# Microcontroller.net
KiCad netlist of a schematic drawn in Altium Designer
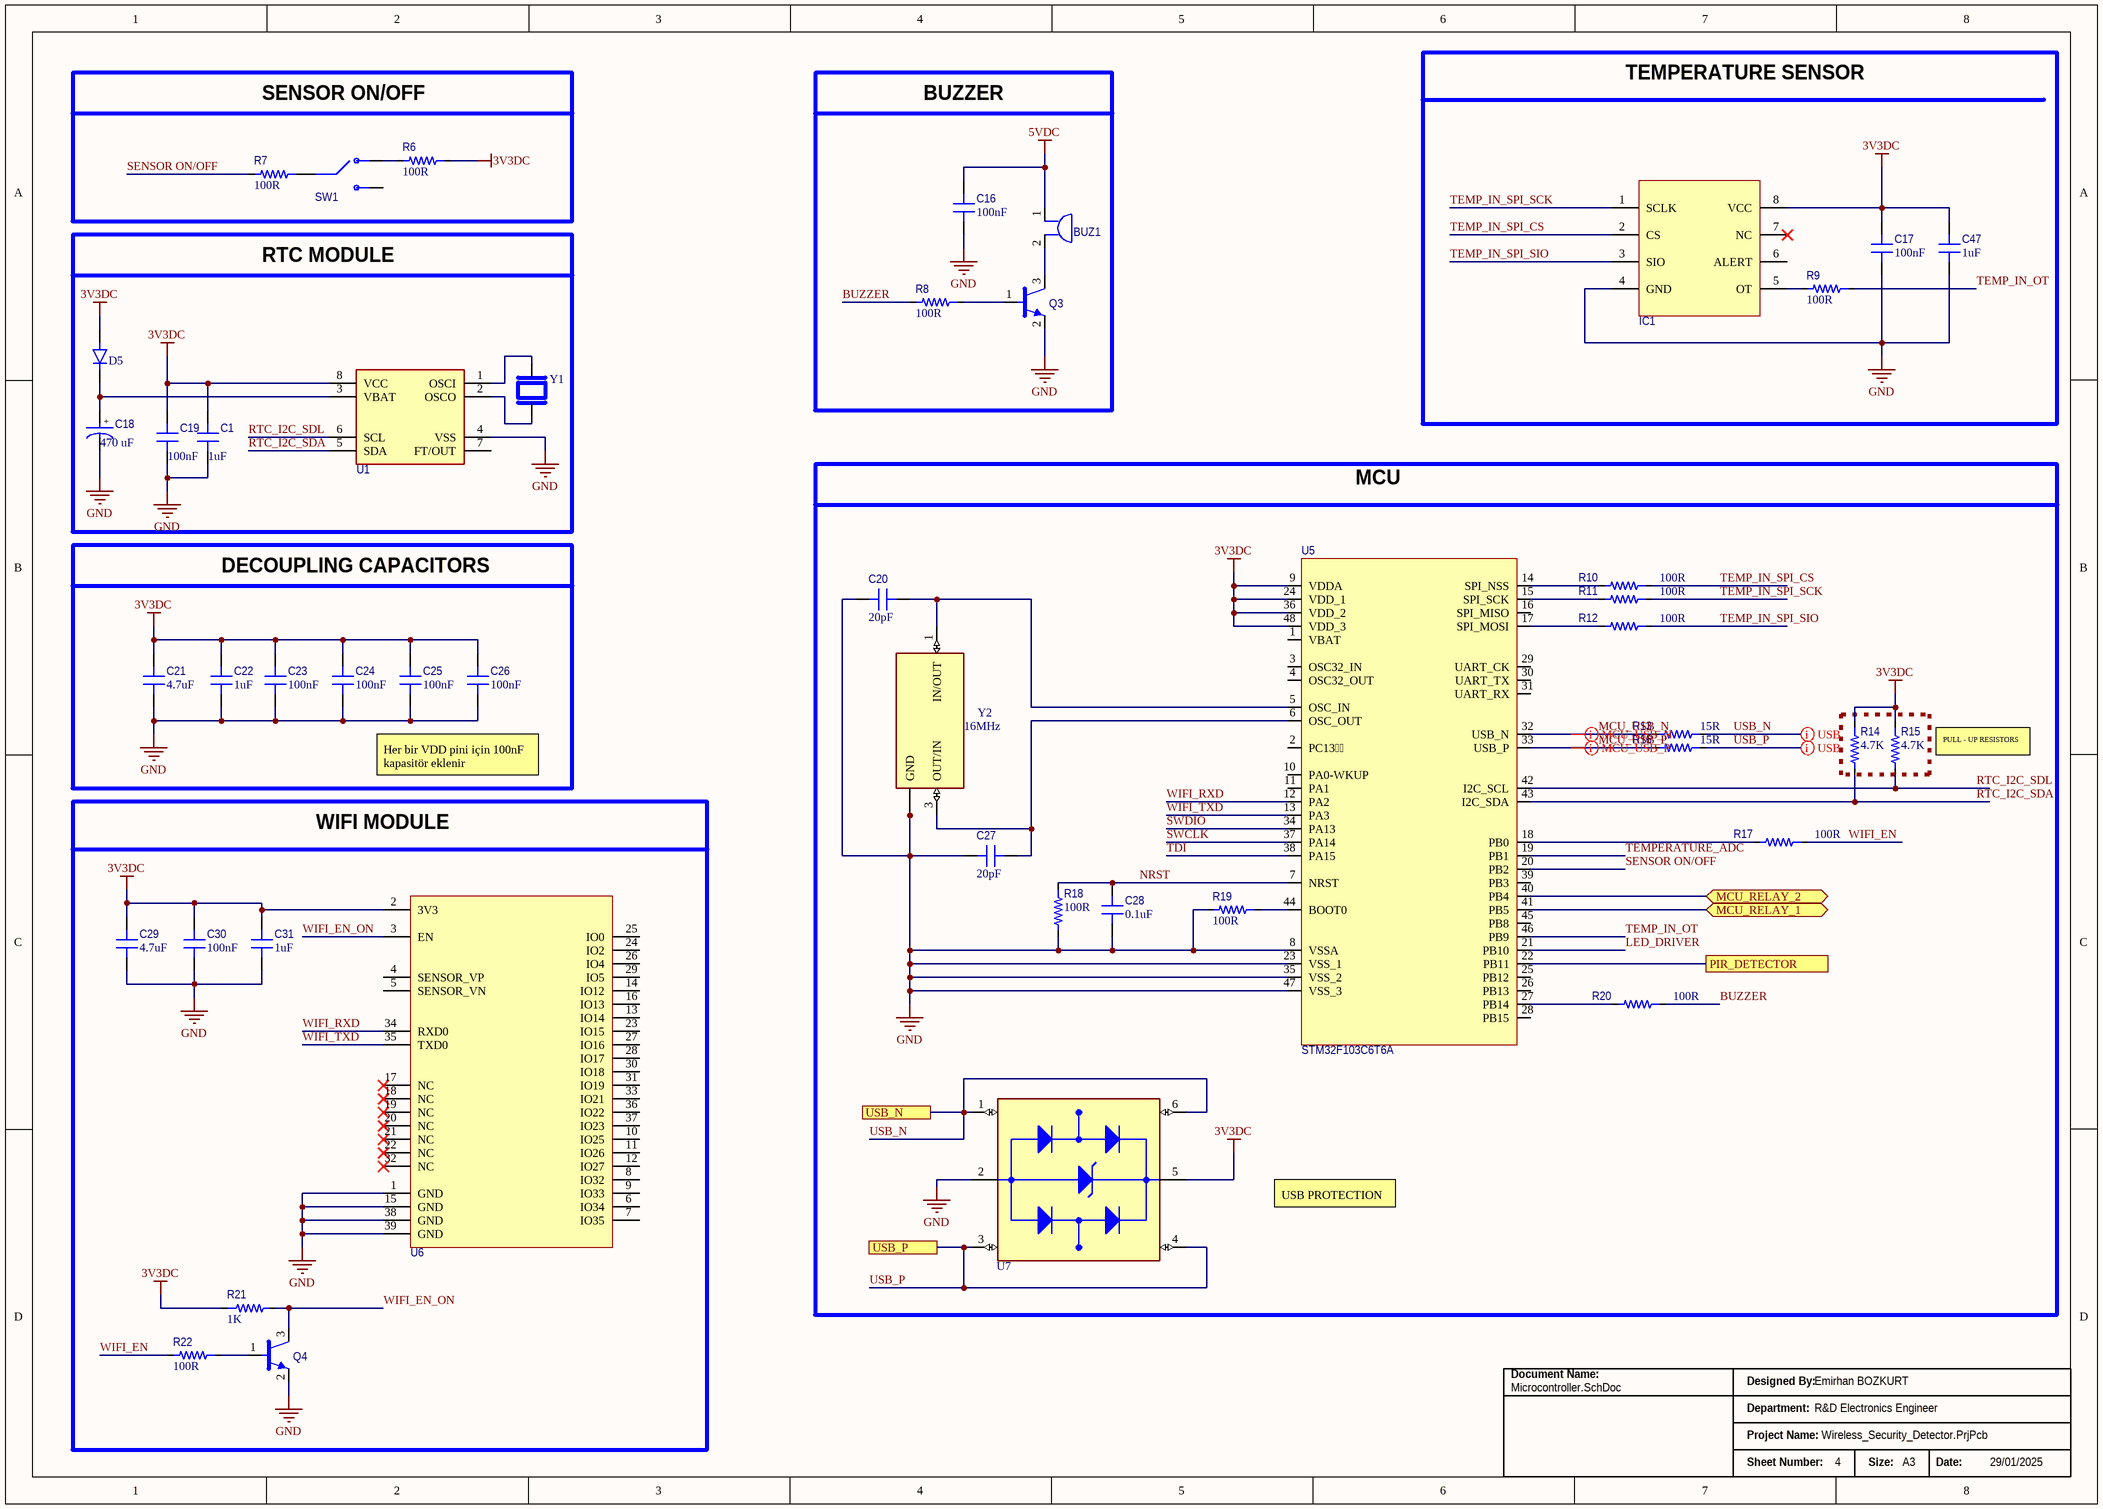
[diagram p0: Microcontroller.SchDoc]

(export (version "E")
  (design (tool "Eeschema 10.0.6"))
  (components
    (comp (ref "BUZ1")
      (value "CMI-9605IC-0580T")
      (footprint "CMI-9605IC-0580T")
      (description "BUZZER MAGNETIC 5V 9.6MM TH")
      (fields (field (name "DESIGNED BY") "Emirhan Bozkurt"))
      (libsource (lib "Emirhan's") (part "CMI-9605IC-0580T"))
    )
    (comp (ref "C1")
      (value "1uF")
      (footprint "CAP_0805")
      (description "CAP CER 1uF 25V X5R 0805")
      (fields
        (field (name "MANUFACTURER") "Samsung Electro-Mechanics")
        (field (name "Comment") "CL21B105KBFNNNE")
        (field (name "DESIGNED BY") "Emirhan Bozkurt")
      )
      (libsource (lib "Emirhan's") (part "CAP CER 1uF 0805"))
    )
    (comp (ref "C16")
      (value "100nF")
      (footprint "CAP_0805")
      (description "CAP CER 0.1uF 50V X7R 0805")
      (fields (field (name "Comment") "1276-1003-2-ND") (field (name "DESIGNED BY") "Emirhan Bozkurt"))
      (libsource (lib "Emirhan's") (part "CAP CER 100nF 0805"))
    )
    (comp (ref "C17")
      (value "100nF")
      (footprint "CAP_0805")
      (description "CAP CER 0.1uF 50V X7R 0805")
      (fields (field (name "Comment") "1276-1003-2-ND") (field (name "DESIGNED BY") "Emirhan Bozkurt"))
      (libsource (lib "Emirhan's") (part "CAP CER 100nF 0805"))
    )
    (comp (ref "C18")
      (value "470 uF")
      (footprint "CAP_ALU_470UF_SMD")
      (description "CAP ALUM POLY 470uF 20% 25V SMD")
      (fields
        (field (name "MANUFACTURER") "Nichicon")
        (field (name "Comment") "PCR1E471MCL1GS")
        (field (name "DESIGNED BY") "Emirhan Bozkurt")
      )
      (libsource (lib "Emirhan's") (part "CAP ALU 470uF SMD"))
    )
    (comp (ref "C19")
      (value "100nF")
      (footprint "CAP_0805")
      (description "CAP CER 0.1uF 50V X7R 0805")
      (fields (field (name "Comment") "1276-1003-2-ND") (field (name "DESIGNED BY") "Emirhan Bozkurt"))
      (libsource (lib "Emirhan's") (part "CAP CER 100nF 0805"))
    )
    (comp (ref "C20")
      (value "20pF")
      (footprint "CAP_0603")
      (description "CAP CER 20pF 50V C0G/NP0 0603")
      (fields
        (field (name "MANUFACTURER") "Samsung Electro-Mechanics")
        (field (name "Comment") "C0603C104K4RACTU")
        (field (name "DESIGNED BY") "Emirhan Bozkurt")
      )
      (libsource (lib "Emirhan's") (part "CAP CER 20pF 0603"))
    )
    (comp (ref "C21")
      (value "4.7uF")
      (footprint "CAP_0805")
      (description "CAP CER 4.7uF 25V X5R 0805")
      (fields
        (field (name "MANUFACTURER") "Samsung Electro-Mechanics")
        (field (name "Comment") "CL21A475KAQNNNE")
        (field (name "DESIGNED BY") "Emirhan Bozkurt")
      )
      (libsource (lib "Emirhan's") (part "CAP CER 4.7uF 0805"))
    )
    (comp (ref "C22")
      (value "1uF")
      (footprint "CAP_0805")
      (description "CAP CER 1uF 25V X5R 0805")
      (fields
        (field (name "MANUFACTURER") "Samsung Electro-Mechanics")
        (field (name "Comment") "CL21B105KBFNNNE")
        (field (name "DESIGNED BY") "Emirhan Bozkurt")
      )
      (libsource (lib "Emirhan's") (part "CAP CER 1uF 0805"))
    )
    (comp (ref "C23")
      (value "100nF")
      (footprint "CAP_0805")
      (description "CAP CER 0.1uF 50V X7R 0805")
      (fields (field (name "Comment") "1276-1003-2-ND") (field (name "DESIGNED BY") "Emirhan Bozkurt"))
      (libsource (lib "Emirhan's") (part "CAP CER 100nF 0805"))
    )
    (comp (ref "C24")
      (value "100nF")
      (footprint "CAP_0805")
      (description "CAP CER 0.1uF 50V X7R 0805")
      (fields (field (name "Comment") "1276-1003-2-ND") (field (name "DESIGNED BY") "Emirhan Bozkurt"))
      (libsource (lib "Emirhan's") (part "CAP CER 100nF 0805"))
    )
    (comp (ref "C25")
      (value "100nF")
      (footprint "CAP_0805")
      (description "CAP CER 0.1uF 50V X7R 0805")
      (fields (field (name "Comment") "1276-1003-2-ND") (field (name "DESIGNED BY") "Emirhan Bozkurt"))
      (libsource (lib "Emirhan's") (part "CAP CER 100nF 0805"))
    )
    (comp (ref "C26")
      (value "100nF")
      (footprint "CAP_0805")
      (description "CAP CER 0.1uF 50V X7R 0805")
      (fields (field (name "Comment") "1276-1003-2-ND") (field (name "DESIGNED BY") "Emirhan Bozkurt"))
      (libsource (lib "Emirhan's") (part "CAP CER 100nF 0805"))
    )
    (comp (ref "C27")
      (value "20pF")
      (footprint "CAP_0603")
      (description "CAP CER 20pF 50V C0G/NP0 0603")
      (fields
        (field (name "MANUFACTURER") "Samsung Electro-Mechanics")
        (field (name "Comment") "C0603C104K4RACTU")
        (field (name "DESIGNED BY") "Emirhan Bozkurt")
      )
      (libsource (lib "Emirhan's") (part "CAP CER 20pF 0603"))
    )
    (comp (ref "C28")
      (value "0.1uF")
      (footprint "CAP_0603")
      (description "CAP CER 0.1uF 16V X7R 0603")
      (fields
        (field (name "MANUFACTURER") "Samsung Electro-Mechanics")
        (field (name "Comment") "C0603C104K4RACTU")
        (field (name "DESIGNED BY") "Emirhan Bozkurt")
      )
      (libsource (lib "Emirhan's") (part "CAP CER 0.1uF 0603"))
    )
    (comp (ref "C29")
      (value "4.7uF")
      (footprint "CAP_0805")
      (description "CAP CER 4.7uF 25V X5R 0805")
      (fields
        (field (name "MANUFACTURER") "Samsung Electro-Mechanics")
        (field (name "Comment") "CL21A475KAQNNNE")
        (field (name "DESIGNED BY") "Emirhan Bozkurt")
      )
      (libsource (lib "Emirhan's") (part "CAP CER 4.7uF 0805"))
    )
    (comp (ref "C30")
      (value "100nF")
      (footprint "CAP_0805")
      (description "CAP CER 0.1uF 50V X7R 0805")
      (fields (field (name "Comment") "1276-1003-2-ND") (field (name "DESIGNED BY") "Emirhan Bozkurt"))
      (libsource (lib "Emirhan's") (part "CAP CER 100nF 0805"))
    )
    (comp (ref "C31")
      (value "1uF")
      (footprint "CAP_0805")
      (description "CAP CER 1uF 25V X5R 0805")
      (fields
        (field (name "MANUFACTURER") "Samsung Electro-Mechanics")
        (field (name "Comment") "CL21B105KBFNNNE")
        (field (name "DESIGNED BY") "Emirhan Bozkurt")
      )
      (libsource (lib "Emirhan's") (part "CAP CER 1uF 0805"))
    )
    (comp (ref "C47")
      (value "1uF")
      (footprint "CAP_0805")
      (description "CAP CER 1uF 25V X5R 0805")
      (fields
        (field (name "MANUFACTURER") "Samsung Electro-Mechanics")
        (field (name "Comment") "CL21B105KBFNNNE")
        (field (name "DESIGNED BY") "Emirhan Bozkurt")
      )
      (libsource (lib "Emirhan's") (part "CAP CER 1uF 0805"))
    )
    (comp (ref "D5")
      (value "1N4148WS")
      (footprint "1N4148WS")
      (description "DIODE STANDARD 75V 150MA SOD323F")
      (fields
        (field (name "MANUFACTURER") "Diotec Semiconductor")
        (field (name "DESIGNED BY") "Emirhan Bozkurt")
      )
      (libsource (lib "Emirhan's") (part "1N4148WS"))
    )
    (comp (ref "IC1")
      (value "MAX6662MSA+")
      (footprint "SOIC-8")
      (description "TEMPERATURE SENSOR DIGITAL REMOTE 8SOIC")
      (fields (field (name "DESIGNED BY") "Emirhan Bozkurt"))
      (libsource (lib "Emirhan's") (part "MAX6662MSA+"))
    )
    (comp (ref "Q3")
      (value "MMBT3904-7-F")
      (footprint "SOT-23F")
      (description "TRANS NPN 40V 0.2A SOT-23-3")
      (libsource (lib "Emirhan's") (part "MMBT3904-7-F"))
    )
    (comp (ref "Q4")
      (value "MMBT3904-7-F")
      (footprint "SOT-23F")
      (description "TRANS NPN 40V 0.2A SOT-23-3")
      (libsource (lib "Emirhan's") (part "MMBT3904-7-F"))
    )
    (comp (ref "R6")
      (value "100R")
      (footprint "RES_0603")
      (description "RES 100 OHM 1% 1/10W 0603")
      (fields
        (field (name "SUPPIER PART NUMBER") "311-100HRTR-ND")
        (field (name "MANUFACTURER") "YAGEO")
        (field (name "DESIGNED BY") "Emirhan Bozkurt")
      )
      (libsource (lib "Emirhan's") (part "RES 100R 0603"))
    )
    (comp (ref "R7")
      (value "100R")
      (footprint "RES_0603")
      (description "RES 100 OHM 1% 1/10W 0603")
      (fields
        (field (name "SUPPIER PART NUMBER") "311-100HRTR-ND")
        (field (name "MANUFACTURER") "YAGEO")
        (field (name "DESIGNED BY") "Emirhan Bozkurt")
      )
      (libsource (lib "Emirhan's") (part "RES 100R 0603"))
    )
    (comp (ref "R8")
      (value "100R")
      (footprint "RES_0603")
      (description "RES 100 OHM 1% 1/10W 0603")
      (fields
        (field (name "SUPPIER PART NUMBER") "311-100HRTR-ND")
        (field (name "MANUFACTURER") "YAGEO")
        (field (name "DESIGNED BY") "Emirhan Bozkurt")
      )
      (libsource (lib "Emirhan's") (part "RES 100R 0603"))
    )
    (comp (ref "R9")
      (value "100R")
      (footprint "RES_0603")
      (description "RES 100 OHM 1% 1/10W 0603")
      (fields
        (field (name "SUPPIER PART NUMBER") "311-100HRTR-ND")
        (field (name "MANUFACTURER") "YAGEO")
        (field (name "DESIGNED BY") "Emirhan Bozkurt")
      )
      (libsource (lib "Emirhan's") (part "RES 100R 0603"))
    )
    (comp (ref "R10")
      (value "100R")
      (footprint "RES_0603")
      (description "RES 100 OHM 1% 1/10W 0603")
      (fields
        (field (name "SUPPIER PART NUMBER") "311-100HRTR-ND")
        (field (name "MANUFACTURER") "YAGEO")
        (field (name "DESIGNED BY") "Emirhan Bozkurt")
      )
      (libsource (lib "Emirhan's") (part "RES 100R 0603"))
    )
    (comp (ref "R11")
      (value "100R")
      (footprint "RES_0603")
      (description "RES 100 OHM 1% 1/10W 0603")
      (fields
        (field (name "SUPPIER PART NUMBER") "311-100HRTR-ND")
        (field (name "MANUFACTURER") "YAGEO")
        (field (name "DESIGNED BY") "Emirhan Bozkurt")
      )
      (libsource (lib "Emirhan's") (part "RES 100R 0603"))
    )
    (comp (ref "R12")
      (value "100R")
      (footprint "RES_0603")
      (description "RES 100 OHM 1% 1/10W 0603")
      (fields
        (field (name "SUPPIER PART NUMBER") "311-100HRTR-ND")
        (field (name "MANUFACTURER") "YAGEO")
        (field (name "DESIGNED BY") "Emirhan Bozkurt")
      )
      (libsource (lib "Emirhan's") (part "RES 100R 0603"))
    )
    (comp (ref "R13")
      (value "15R")
      (footprint "RES_0603")
      (description "RES 15 OHM 1% 1/10W 0603")
      (fields
        (field (name "SUPPIER PART NUMBER") "311-15.0HRTR-ND")
        (field (name "MANUFACTURER") "YAGEO")
        (field (name "DESIGNED BY") "Emirhan Bozkurt")
      )
      (libsource (lib "Emirhan's") (part "RES 15R 0603"))
    )
    (comp (ref "R14")
      (value "4.7K")
      (footprint "RES_0603")
      (description "RES 4K7 OHM 1% 1/10W 0603")
      (fields
        (field (name "SUPPIER PART NUMBER") "311-4.70KHRCT-ND")
        (field (name "MANUFACTURER") "YAGEO")
        (field (name "DESIGNED BY") "Emirhan Bozkurt")
      )
      (libsource (lib "Emirhan's") (part "RES 4K7 0603"))
    )
    (comp (ref "R15")
      (value "4.7K")
      (footprint "RES_0603")
      (description "RES 4K7 OHM 1% 1/10W 0603")
      (fields
        (field (name "SUPPIER PART NUMBER") "311-4.70KHRCT-ND")
        (field (name "MANUFACTURER") "YAGEO")
        (field (name "DESIGNED BY") "Emirhan Bozkurt")
      )
      (libsource (lib "Emirhan's") (part "RES 4K7 0603"))
    )
    (comp (ref "R16")
      (value "15R")
      (footprint "RES_0603")
      (description "RES 15 OHM 1% 1/10W 0603")
      (fields
        (field (name "SUPPIER PART NUMBER") "311-15.0HRTR-ND")
        (field (name "MANUFACTURER") "YAGEO")
        (field (name "DESIGNED BY") "Emirhan Bozkurt")
      )
      (libsource (lib "Emirhan's") (part "RES 15R 0603"))
    )
    (comp (ref "R17")
      (value "100R")
      (footprint "RES_0603")
      (description "RES 100 OHM 1% 1/10W 0603")
      (fields
        (field (name "SUPPIER PART NUMBER") "311-100HRTR-ND")
        (field (name "MANUFACTURER") "YAGEO")
        (field (name "DESIGNED BY") "Emirhan Bozkurt")
      )
      (libsource (lib "Emirhan's") (part "RES 100R 0603"))
    )
    (comp (ref "R18")
      (value "100R")
      (footprint "RES_0603")
      (description "RES 100 OHM 1% 1/10W 0603")
      (fields
        (field (name "SUPPIER PART NUMBER") "311-100HRTR-ND")
        (field (name "MANUFACTURER") "YAGEO")
        (field (name "DESIGNED BY") "Emirhan Bozkurt")
      )
      (libsource (lib "Emirhan's") (part "RES 100R 0603"))
    )
    (comp (ref "R19")
      (value "100R")
      (footprint "RES_0603")
      (description "RES 100 OHM 1% 1/10W 0603")
      (fields
        (field (name "SUPPIER PART NUMBER") "311-100HRTR-ND")
        (field (name "MANUFACTURER") "YAGEO")
        (field (name "DESIGNED BY") "Emirhan Bozkurt")
      )
      (libsource (lib "Emirhan's") (part "RES 100R 0603"))
    )
    (comp (ref "R20")
      (value "100R")
      (footprint "RES_0603")
      (description "RES 100 OHM 1% 1/10W 0603")
      (fields
        (field (name "SUPPIER PART NUMBER") "311-100HRTR-ND")
        (field (name "MANUFACTURER") "YAGEO")
        (field (name "DESIGNED BY") "Emirhan Bozkurt")
      )
      (libsource (lib "Emirhan's") (part "RES 100R 0603"))
    )
    (comp (ref "R21")
      (value "1K")
      (footprint "RES_0603")
      (description "RES 1K 1% 1/10W 0603")
      (fields
        (field (name "SUPPIER PART NUMBER") "311-1.00KHRCT-ND")
        (field (name "MANUFACTURER") "YAGEO")
        (field (name "DESIGNED BY") "Emirhan Bozkurt")
      )
      (libsource (lib "Emirhan's") (part "RES 1K 0603"))
    )
    (comp (ref "R22")
      (value "100R")
      (footprint "RES_0603")
      (description "RES 100 OHM 1% 1/10W 0603")
      (fields
        (field (name "SUPPIER PART NUMBER") "311-100HRTR-ND")
        (field (name "MANUFACTURER") "YAGEO")
        (field (name "DESIGNED BY") "Emirhan Bozkurt")
      )
      (libsource (lib "Emirhan's") (part "RES 100R 0603"))
    )
    (comp (ref "SW1")
      (value "EG1215AA")
      (footprint "EG1215AA")
      (description "SWITCH SLIDE SPDT 25MA 24V")
      (fields (field (name "DESIGNED BY") "Emirhan Bozkurt"))
      (libsource (lib "Emirhan's") (part "EG1215AA"))
    )
    (comp (ref "U1")
      (value "M41T00M6F")
      (footprint "SOIC-8")
      (description "IC RTC CLK/CALENDAR I2C 8SOIC")
      (fields (field (name "DESIGNED BY") "Emirhan BOZKURT"))
      (libsource (lib "Emirhan's") (part "M41T00M6F"))
    )
    (comp (ref "U5")
      (value "STM32F103C6T6A")
      (footprint "LQFP-48")
      (description "IC MCU 32BIT 32KB FLASH 48LQFP")
      (fields (field (name "VOLTAGE") "2V ~ 3.6V") (field (name "DESIGNED BY") "Emirhan Bozkurt"))
      (libsource (lib "Emirhan's") (part "STM32F103C6T6A"))
    )
    (comp (ref "U6")
      (value "ESP32-WROOM-32E-N4")
      (footprint "ESP32-WROOM-32E")
      (description "RF TXRX MOD BT WIFI TH SMD")
      (fields (field (name "DESIGNED BY") "Emirhan Bozkurt"))
      (libsource (lib "Emirhan's") (part "ESP32-WROOM-32E-N4"))
    )
    (comp (ref "U7")
      (value "USBLC6-2SC6")
      (footprint "SOT95P280X145-6N")
      (description "TVS DIODE 5.25VWM 17VC SOT23-6")
      (fields
        (field (name "MANUFACTURER") "STMicroelectronics")
        (field (name "DESIGNED BY") "Emirhan Bozkurt")
      )
      (libsource (lib "Emirhan's") (part "USB PROTECTION"))
    )
    (comp (ref "Y1")
      (value "ABS05-32.768KHZ-T")
      (footprint "XTAL_ABS05-32.768KHZ-T")
      (description "CRYSTAL 32.7680KHZ 12.5PF SMD")
      (fields
        (field (name "SUPPLER PART NUMBER") "535-11899-2-ND")
        (field (name "DESIGNED BY") "Emirhan Bozkurt")
      )
      (libsource (lib "Emirhan's") (part "ABS05-32.768KHZ-T"))
    )
    (comp (ref "Y2")
      (value "16MHz")
      (footprint "XTAL_ECS-160-20-30B-TR")
      (description "CRYSTAL 16.0000MHZ 20PF SMD")
      (fields (field (name "Comment") "ECS-160-20-30B-TR") (field (name "DESIGNED BY") "Emirhan Bozkurt"))
      (libsource (lib "Emirhan's") (part "ECS-160-20-30B-TR"))
    )
  )
  (nets
    (net (code "1") (name "/BUZZER") (class "Default")
      (node (ref "R20") (pin "2") (pinfunction "2_2") (pintype "passive"))
      (node (ref "R8") (pin "1") (pinfunction "1_1") (pintype "passive"))
    )
    (net (code "2") (name "/LED_DRIVER") (class "Default")
      (node (ref "U5") (pin "21") (pinfunction "PB10_21") (pintype "passive"))
    )
    (net (code "3") (name "/MCU_RELAY_1") (class "Default")
      (node (ref "U5") (pin "41") (pinfunction "PB5_41") (pintype "passive"))
    )
    (net (code "4") (name "/MCU_RELAY_2") (class "Default")
      (node (ref "U5") (pin "40") (pinfunction "PB4_40") (pintype "passive"))
    )
    (net (code "5") (name "/MCU_USB_N") (class "Default")
      (node (ref "R13") (pin "1") (pinfunction "1_1") (pintype "passive"))
      (node (ref "U5") (pin "32") (pinfunction "USB_N_32") (pintype "passive"))
    )
    (net (code "6") (name "/MCU_USB_P") (class "Default")
      (node (ref "R16") (pin "1") (pinfunction "1_1") (pintype "passive"))
      (node (ref "U5") (pin "33") (pinfunction "USB_P_33") (pintype "passive"))
    )
    (net (code "7") (name "/NRST") (class "Default")
      (node (ref "C28") (pin "2") (pinfunction "2_2") (pintype "passive"))
      (node (ref "R18") (pin "2") (pinfunction "2_2") (pintype "passive"))
      (node (ref "U5") (pin "7") (pinfunction "NRST_7") (pintype "passive"))
    )
    (net (code "8") (name "/PIR_DETECTOR") (class "Default")
      (node (ref "U5") (pin "22") (pinfunction "PB11_22") (pintype "passive"))
    )
    (net (code "9") (name "/RTC_I2C_SDA") (class "Default")
      (node (ref "R14") (pin "1") (pinfunction "1_1") (pintype "passive"))
      (node (ref "U1") (pin "5") (pinfunction "SDA_5") (pintype "passive"))
      (node (ref "U5") (pin "43") (pinfunction "I2C_SDA_43") (pintype "passive"))
    )
    (net (code "10") (name "/RTC_I2C_SDL") (class "Default")
      (node (ref "R15") (pin "1") (pinfunction "1_1") (pintype "passive"))
      (node (ref "U1") (pin "6") (pinfunction "SCL_6") (pintype "passive"))
      (node (ref "U5") (pin "42") (pinfunction "I2C_SCL_42") (pintype "passive"))
    )
    (net (code "11") (name "/SENSOR ON{slash}OFF") (class "Default")
      (node (ref "R7") (pin "1") (pinfunction "1_1") (pintype "passive"))
      (node (ref "U5") (pin "20") (pinfunction "PB2_20") (pintype "passive"))
    )
    (net (code "12") (name "/SWCLK") (class "Default")
      (node (ref "U5") (pin "37") (pinfunction "PA14_37") (pintype "passive"))
    )
    (net (code "13") (name "/SWDIO") (class "Default")
      (node (ref "U5") (pin "34") (pinfunction "PA13_34") (pintype "passive"))
    )
    (net (code "14") (name "/TDI") (class "Default")
      (node (ref "U5") (pin "38") (pinfunction "PA15_38") (pintype "passive"))
    )
    (net (code "15") (name "/TEMPERATURE_ADC") (class "Default")
      (node (ref "U5") (pin "19") (pinfunction "PB1_19") (pintype "passive"))
    )
    (net (code "16") (name "/TEMP_IN_OT") (class "Default")
      (node (ref "R9") (pin "2") (pinfunction "2_2") (pintype "passive"))
      (node (ref "U5") (pin "46") (pinfunction "PB9_46") (pintype "passive"))
    )
    (net (code "17") (name "/TEMP_IN_SPI_CS") (class "Default")
      (node (ref "IC1") (pin "2") (pinfunction "CS_2") (pintype "passive"))
      (node (ref "R10") (pin "2") (pinfunction "2_2") (pintype "passive"))
    )
    (net (code "18") (name "/TEMP_IN_SPI_SCK") (class "Default")
      (node (ref "IC1") (pin "1") (pinfunction "SCLK_1") (pintype "passive"))
      (node (ref "R11") (pin "2") (pinfunction "2_2") (pintype "passive"))
    )
    (net (code "19") (name "/TEMP_IN_SPI_SIO") (class "Default")
      (node (ref "IC1") (pin "3") (pinfunction "SIO_3") (pintype "passive"))
      (node (ref "R12") (pin "2") (pinfunction "2_2") (pintype "passive"))
    )
    (net (code "20") (name "/USB_N") (class "Default")
      (node (ref "R13") (pin "2") (pinfunction "2_2") (pintype "passive"))
      (node (ref "U7") (pin "1") (pinfunction "I/O1_IN_1") (pintype "bidirectional"))
      (node (ref "U7") (pin "6") (pinfunction "I/O1_OUT_6") (pintype "bidirectional"))
    )
    (net (code "21") (name "/USB_P") (class "Default")
      (node (ref "R16") (pin "2") (pinfunction "2_2") (pintype "passive"))
      (node (ref "U7") (pin "3") (pinfunction "I/O2_IN_3") (pintype "bidirectional"))
      (node (ref "U7") (pin "4") (pinfunction "I/O2_OUT_4") (pintype "bidirectional"))
    )
    (net (code "22") (name "/WIFI_EN") (class "Default")
      (node (ref "R17") (pin "2") (pinfunction "2_2") (pintype "passive"))
      (node (ref "R22") (pin "1") (pinfunction "1_1") (pintype "passive"))
    )
    (net (code "23") (name "/WIFI_EN_ON") (class "Default")
      (node (ref "Q4") (pin "3") (pinfunction "C_3") (pintype "passive"))
      (node (ref "R21") (pin "1") (pinfunction "1_1") (pintype "passive"))
      (node (ref "U6") (pin "3") (pinfunction "EN_3") (pintype "passive"))
    )
    (net (code "24") (name "/WIFI_RXD") (class "Default")
      (node (ref "U5") (pin "12") (pinfunction "PA2_12") (pintype "passive"))
      (node (ref "U6") (pin "34") (pinfunction "RXD0_34") (pintype "passive"))
    )
    (net (code "25") (name "/WIFI_TXD") (class "Default")
      (node (ref "U5") (pin "13") (pinfunction "PA3_13") (pintype "passive"))
      (node (ref "U6") (pin "35") (pinfunction "TXD0_35") (pintype "passive"))
    )
    (net (code "26") (name "3V3DC") (class "Default")
      (node (ref "C1") (pin "2") (pinfunction "2_2") (pintype "passive"))
      (node (ref "C17") (pin "2") (pinfunction "2_2") (pintype "passive"))
      (node (ref "C19") (pin "2") (pinfunction "2_2") (pintype "passive"))
      (node (ref "C21") (pin "2") (pinfunction "2_2") (pintype "passive"))
      (node (ref "C22") (pin "2") (pinfunction "2_2") (pintype "passive"))
      (node (ref "C23") (pin "2") (pinfunction "2_2") (pintype "passive"))
      (node (ref "C24") (pin "2") (pinfunction "2_2") (pintype "passive"))
      (node (ref "C25") (pin "2") (pinfunction "2_2") (pintype "passive"))
      (node (ref "C26") (pin "2") (pinfunction "2_2") (pintype "passive"))
      (node (ref "C29") (pin "2") (pinfunction "2_2") (pintype "passive"))
      (node (ref "C30") (pin "2") (pinfunction "2_2") (pintype "passive"))
      (node (ref "C31") (pin "2") (pinfunction "2_2") (pintype "passive"))
      (node (ref "C47") (pin "2") (pinfunction "2_2") (pintype "passive"))
      (node (ref "D5") (pin "A") (pinfunction "A_A") (pintype "passive"))
      (node (ref "IC1") (pin "8") (pinfunction "VCC_8") (pintype "passive"))
      (node (ref "R14") (pin "2") (pinfunction "2_2") (pintype "passive"))
      (node (ref "R15") (pin "2") (pinfunction "2_2") (pintype "passive"))
      (node (ref "R21") (pin "2") (pinfunction "2_2") (pintype "passive"))
      (node (ref "R6") (pin "2") (pinfunction "2_2") (pintype "passive"))
      (node (ref "U1") (pin "8") (pinfunction "VCC_8") (pintype "passive"))
      (node (ref "U5") (pin "24") (pinfunction "VDD_1_24") (pintype "passive"))
      (node (ref "U5") (pin "36") (pinfunction "VDD_2_36") (pintype "passive"))
      (node (ref "U5") (pin "48") (pinfunction "VDD_3_48") (pintype "passive"))
      (node (ref "U5") (pin "9") (pinfunction "VDDA_9") (pintype "passive"))
      (node (ref "U6") (pin "2") (pinfunction "3V3_2") (pintype "passive"))
      (node (ref "U7") (pin "5") (pinfunction "VBUS_5") (pintype "power_in"))
    )
    (net (code "27") (name "5VDC") (class "Default")
      (node (ref "BUZ1") (pin "1") (pinfunction "1_1") (pintype "passive"))
      (node (ref "C16") (pin "2") (pinfunction "2_2") (pintype "passive"))
    )
    (net (code "28") (name "GND") (class "Default")
      (node (ref "C1") (pin "1") (pinfunction "1_1") (pintype "passive"))
      (node (ref "C16") (pin "1") (pinfunction "1_1") (pintype "passive"))
      (node (ref "C17") (pin "1") (pinfunction "1_1") (pintype "passive"))
      (node (ref "C18") (pin "2") (pinfunction "2_2") (pintype "passive"))
      (node (ref "C19") (pin "1") (pinfunction "1_1") (pintype "passive"))
      (node (ref "C20") (pin "1") (pinfunction "1_1") (pintype "passive"))
      (node (ref "C21") (pin "1") (pinfunction "1_1") (pintype "passive"))
      (node (ref "C22") (pin "1") (pinfunction "1_1") (pintype "passive"))
      (node (ref "C23") (pin "1") (pinfunction "1_1") (pintype "passive"))
      (node (ref "C24") (pin "1") (pinfunction "1_1") (pintype "passive"))
      (node (ref "C25") (pin "1") (pinfunction "1_1") (pintype "passive"))
      (node (ref "C26") (pin "1") (pinfunction "1_1") (pintype "passive"))
      (node (ref "C27") (pin "1") (pinfunction "1_1") (pintype "passive"))
      (node (ref "C28") (pin "1") (pinfunction "1_1") (pintype "passive"))
      (node (ref "C29") (pin "1") (pinfunction "1_1") (pintype "passive"))
      (node (ref "C30") (pin "1") (pinfunction "1_1") (pintype "passive"))
      (node (ref "C31") (pin "1") (pinfunction "1_1") (pintype "passive"))
      (node (ref "C47") (pin "1") (pinfunction "1_1") (pintype "passive"))
      (node (ref "IC1") (pin "4") (pinfunction "GND_4") (pintype "passive"))
      (node (ref "Q3") (pin "2") (pinfunction "E_2") (pintype "passive"))
      (node (ref "Q4") (pin "2") (pinfunction "E_2") (pintype "passive"))
      (node (ref "R18") (pin "1") (pinfunction "1_1") (pintype "passive"))
      (node (ref "R19") (pin "1") (pinfunction "1_1") (pintype "passive"))
      (node (ref "U1") (pin "4") (pinfunction "VSS_4") (pintype "passive"))
      (node (ref "U5") (pin "23") (pinfunction "VSS_1_23") (pintype "passive"))
      (node (ref "U5") (pin "35") (pinfunction "VSS_2_35") (pintype "passive"))
      (node (ref "U5") (pin "47") (pinfunction "VSS_3_47") (pintype "passive"))
      (node (ref "U5") (pin "8") (pinfunction "VSSA_8") (pintype "passive"))
      (node (ref "U6") (pin "1") (pinfunction "GND_1") (pintype "passive"))
      (node (ref "U6") (pin "15") (pinfunction "GND_15") (pintype "passive"))
      (node (ref "U6") (pin "38") (pinfunction "GND_38") (pintype "passive"))
      (node (ref "U6") (pin "39") (pinfunction "GND_39") (pintype "passive"))
      (node (ref "U7") (pin "2") (pinfunction "GND_2") (pintype "power_in"))
      (node (ref "Y2") (pin "2") (pinfunction "GND_2") (pintype "power_in"))
      (node (ref "Y2") (pin "4") (pinfunction "GND_4") (pintype "power_in"))
    )
    (net (code "29") (name "Net-(IC1-OT)") (class "Default")
      (node (ref "IC1") (pin "5") (pinfunction "OT_5") (pintype "passive"))
      (node (ref "R9") (pin "1") (pinfunction "1_1") (pintype "passive"))
    )
    (net (code "30") (name "Net-(Q3-B)") (class "Default")
      (node (ref "Q3") (pin "1") (pinfunction "B_1") (pintype "passive"))
      (node (ref "R8") (pin "2") (pinfunction "2_2") (pintype "passive"))
    )
    (net (code "31") (name "Net-(Q3-C)") (class "Default")
      (node (ref "BUZ1") (pin "2") (pinfunction "2_2") (pintype "passive"))
      (node (ref "Q3") (pin "3") (pinfunction "C_3") (pintype "passive"))
    )
    (net (code "32") (name "Net-(Q4-B)") (class "Default")
      (node (ref "Q4") (pin "1") (pinfunction "B_1") (pintype "passive"))
      (node (ref "R22") (pin "2") (pinfunction "2_2") (pintype "passive"))
    )
    (net (code "33") (name "Net-(R6-Pad1)") (class "Default")
      (node (ref "R6") (pin "1") (pinfunction "1_1") (pintype "passive"))
      (node (ref "SW1") (pin "1") (pinfunction "1_1") (pintype "passive"))
    )
    (net (code "34") (name "Net-(R7-Pad2)") (class "Default")
      (node (ref "R7") (pin "2") (pinfunction "2_2") (pintype "passive"))
      (node (ref "SW1") (pin "2") (pinfunction "2_2") (pintype "passive"))
    )
    (net (code "35") (name "Net-(U1-OSCI)") (class "Default")
      (node (ref "U1") (pin "1") (pinfunction "OSCI_1") (pintype "passive"))
      (node (ref "Y1") (pin "2") (pinfunction "2_2") (pintype "passive"))
    )
    (net (code "36") (name "Net-(U1-OSCO)") (class "Default")
      (node (ref "U1") (pin "2") (pinfunction "OSCO_2") (pintype "passive"))
      (node (ref "Y1") (pin "1") (pinfunction "1_1") (pintype "passive"))
    )
    (net (code "37") (name "Net-(U1-VBAT)") (class "Default")
      (node (ref "C18") (pin "1") (pinfunction "1_1") (pintype "passive"))
      (node (ref "D5") (pin "C") (pinfunction "C_C") (pintype "passive"))
      (node (ref "U1") (pin "3") (pinfunction "VBAT_3") (pintype "passive"))
    )
    (net (code "38") (name "Net-(U5-BOOT0)") (class "Default")
      (node (ref "R19") (pin "2") (pinfunction "2_2") (pintype "passive"))
      (node (ref "U5") (pin "44") (pinfunction "BOOT0_44") (pintype "passive"))
    )
    (net (code "39") (name "Net-(U5-OSC_IN)") (class "Default")
      (node (ref "C20") (pin "2") (pinfunction "2_2") (pintype "passive"))
      (node (ref "U5") (pin "5") (pinfunction "OSC_IN_5") (pintype "passive"))
      (node (ref "Y2") (pin "1") (pinfunction "IN/OUT_1") (pintype "bidirectional"))
    )
    (net (code "40") (name "Net-(U5-OSC_OUT)") (class "Default")
      (node (ref "C27") (pin "2") (pinfunction "2_2") (pintype "passive"))
      (node (ref "U5") (pin "6") (pinfunction "OSC_OUT_6") (pintype "passive"))
      (node (ref "Y2") (pin "3") (pinfunction "OUT/IN_3") (pintype "bidirectional"))
    )
    (net (code "41") (name "Net-(U5-PB0)") (class "Default")
      (node (ref "R17") (pin "1") (pinfunction "1_1") (pintype "passive"))
      (node (ref "U5") (pin "18") (pinfunction "PB0_18") (pintype "passive"))
    )
    (net (code "42") (name "Net-(U5-PB14)") (class "Default")
      (node (ref "R20") (pin "1") (pinfunction "1_1") (pintype "passive"))
      (node (ref "U5") (pin "27") (pinfunction "PB14_27") (pintype "passive"))
    )
    (net (code "43") (name "Net-(U5-SPI_MOSI)") (class "Default")
      (node (ref "R12") (pin "1") (pinfunction "1_1") (pintype "passive"))
      (node (ref "U5") (pin "17") (pinfunction "SPI_MOSI_17") (pintype "passive"))
    )
    (net (code "44") (name "Net-(U5-SPI_NSS)") (class "Default")
      (node (ref "R10") (pin "1") (pinfunction "1_1") (pintype "passive"))
      (node (ref "U5") (pin "14") (pinfunction "SPI_NSS_14") (pintype "passive"))
    )
    (net (code "45") (name "Net-(U5-SPI_SCK)") (class "Default")
      (node (ref "R11") (pin "1") (pinfunction "1_1") (pintype "passive"))
      (node (ref "U5") (pin "15") (pinfunction "SPI_SCK_15") (pintype "passive"))
    )
    (net (code "46") (name "unconnected-(IC1-ALERT-Pad6)") (class "Default")
      (node (ref "IC1") (pin "6") (pinfunction "ALERT_6") (pintype "passive"))
    )
    (net (code "47") (name "unconnected-(IC1-NC-Pad7)") (class "Default")
      (node (ref "IC1") (pin "7") (pinfunction "NC_7") (pintype "passive+no_connect"))
    )
    (net (code "48") (name "unconnected-(SW1-Pad3)") (class "Default")
      (node (ref "SW1") (pin "3") (pinfunction "3_3") (pintype "passive"))
    )
    (net (code "49") (name "unconnected-(U1-FT{slash}OUT-Pad7)") (class "Default")
      (node (ref "U1") (pin "7") (pinfunction "FT/OUT_7") (pintype "passive"))
    )
    (net (code "50") (name "unconnected-(U5-OSC32_IN-Pad3)") (class "Default")
      (node (ref "U5") (pin "3") (pinfunction "OSC32_IN_3") (pintype "passive"))
    )
    (net (code "51") (name "unconnected-(U5-OSC32_OUT-Pad4)") (class "Default")
      (node (ref "U5") (pin "4") (pinfunction "OSC32_OUT_4") (pintype "passive"))
    )
    (net (code "52") (name "unconnected-(U5-PA0-WKUP-Pad10)") (class "Default")
      (node (ref "U5") (pin "10") (pinfunction "PA0-WKUP_10") (pintype "passive"))
    )
    (net (code "53") (name "unconnected-(U5-PA1-Pad11)") (class "Default")
      (node (ref "U5") (pin "11") (pinfunction "PA1_11") (pintype "passive"))
    )
    (net (code "54") (name "unconnected-(U5-PB3-Pad39)") (class "Default")
      (node (ref "U5") (pin "39") (pinfunction "PB3_39") (pintype "passive"))
    )
    (net (code "55") (name "unconnected-(U5-PB8-Pad45)") (class "Default")
      (node (ref "U5") (pin "45") (pinfunction "PB8_45") (pintype "passive"))
    )
    (net (code "56") (name "unconnected-(U5-PB12-Pad25)") (class "Default")
      (node (ref "U5") (pin "25") (pinfunction "PB12_25") (pintype "passive"))
    )
    (net (code "57") (name "unconnected-(U5-PB13-Pad26)") (class "Default")
      (node (ref "U5") (pin "26") (pinfunction "PB13_26") (pintype "passive"))
    )
    (net (code "58") (name "unconnected-(U5-PB15-Pad28)") (class "Default")
      (node (ref "U5") (pin "28") (pinfunction "PB15_28") (pintype "passive"))
    )
    (net (code "59") (name "unconnected-(U5-PC13-Pad2)") (class "Default")
      (node (ref "U5") (pin "2") (pinfunction "PC13_2") (pintype "passive"))
    )
    (net (code "60") (name "unconnected-(U5-SPI_MISO-Pad16)") (class "Default")
      (node (ref "U5") (pin "16") (pinfunction "SPI_MISO_16") (pintype "passive"))
    )
    (net (code "61") (name "unconnected-(U5-UART_CK-Pad29)") (class "Default")
      (node (ref "U5") (pin "29") (pinfunction "UART_CK_29") (pintype "passive"))
    )
    (net (code "62") (name "unconnected-(U5-UART_RX-Pad31)") (class "Default")
      (node (ref "U5") (pin "31") (pinfunction "UART_RX_31") (pintype "passive"))
    )
    (net (code "63") (name "unconnected-(U5-UART_TX-Pad30)") (class "Default")
      (node (ref "U5") (pin "30") (pinfunction "UART_TX_30") (pintype "passive"))
    )
    (net (code "64") (name "unconnected-(U5-VBAT-Pad1)") (class "Default")
      (node (ref "U5") (pin "1") (pinfunction "VBAT_1") (pintype "passive"))
    )
    (net (code "65") (name "unconnected-(U6-IO0-Pad25)") (class "Default")
      (node (ref "U6") (pin "25") (pinfunction "IO0_25") (pintype "passive"))
    )
    (net (code "66") (name "unconnected-(U6-IO2-Pad24)") (class "Default")
      (node (ref "U6") (pin "24") (pinfunction "IO2_24") (pintype "passive"))
    )
    (net (code "67") (name "unconnected-(U6-IO4-Pad26)") (class "Default")
      (node (ref "U6") (pin "26") (pinfunction "IO4_26") (pintype "passive"))
    )
    (net (code "68") (name "unconnected-(U6-IO5-Pad29)") (class "Default")
      (node (ref "U6") (pin "29") (pinfunction "IO5_29") (pintype "passive"))
    )
    (net (code "69") (name "unconnected-(U6-IO12-Pad14)") (class "Default")
      (node (ref "U6") (pin "14") (pinfunction "IO12_14") (pintype "passive"))
    )
    (net (code "70") (name "unconnected-(U6-IO13-Pad16)") (class "Default")
      (node (ref "U6") (pin "16") (pinfunction "IO13_16") (pintype "passive"))
    )
    (net (code "71") (name "unconnected-(U6-IO14-Pad13)") (class "Default")
      (node (ref "U6") (pin "13") (pinfunction "IO14_13") (pintype "passive"))
    )
    (net (code "72") (name "unconnected-(U6-IO15-Pad23)") (class "Default")
      (node (ref "U6") (pin "23") (pinfunction "IO15_23") (pintype "passive"))
    )
    (net (code "73") (name "unconnected-(U6-IO16-Pad27)") (class "Default")
      (node (ref "U6") (pin "27") (pinfunction "IO16_27") (pintype "passive"))
    )
    (net (code "74") (name "unconnected-(U6-IO17-Pad28)") (class "Default")
      (node (ref "U6") (pin "28") (pinfunction "IO17_28") (pintype "passive"))
    )
    (net (code "75") (name "unconnected-(U6-IO18-Pad30)") (class "Default")
      (node (ref "U6") (pin "30") (pinfunction "IO18_30") (pintype "passive"))
    )
    (net (code "76") (name "unconnected-(U6-IO19-Pad31)") (class "Default")
      (node (ref "U6") (pin "31") (pinfunction "IO19_31") (pintype "passive"))
    )
    (net (code "77") (name "unconnected-(U6-IO21-Pad33)") (class "Default")
      (node (ref "U6") (pin "33") (pinfunction "IO21_33") (pintype "passive"))
    )
    (net (code "78") (name "unconnected-(U6-IO22-Pad36)") (class "Default")
      (node (ref "U6") (pin "36") (pinfunction "IO22_36") (pintype "passive"))
    )
    (net (code "79") (name "unconnected-(U6-IO23-Pad37)") (class "Default")
      (node (ref "U6") (pin "37") (pinfunction "IO23_37") (pintype "passive"))
    )
    (net (code "80") (name "unconnected-(U6-IO25-Pad10)") (class "Default")
      (node (ref "U6") (pin "10") (pinfunction "IO25_10") (pintype "passive"))
    )
    (net (code "81") (name "unconnected-(U6-IO26-Pad11)") (class "Default")
      (node (ref "U6") (pin "11") (pinfunction "IO26_11") (pintype "passive"))
    )
    (net (code "82") (name "unconnected-(U6-IO27-Pad12)") (class "Default")
      (node (ref "U6") (pin "12") (pinfunction "IO27_12") (pintype "passive"))
    )
    (net (code "83") (name "unconnected-(U6-IO32-Pad8)") (class "Default")
      (node (ref "U6") (pin "8") (pinfunction "IO32_8") (pintype "passive"))
    )
    (net (code "84") (name "unconnected-(U6-IO33-Pad9)") (class "Default")
      (node (ref "U6") (pin "9") (pinfunction "IO33_9") (pintype "passive"))
    )
    (net (code "85") (name "unconnected-(U6-IO34-Pad6)") (class "Default")
      (node (ref "U6") (pin "6") (pinfunction "IO34_6") (pintype "passive"))
    )
    (net (code "86") (name "unconnected-(U6-IO35-Pad7)") (class "Default")
      (node (ref "U6") (pin "7") (pinfunction "IO35_7") (pintype "passive"))
    )
    (net (code "87") (name "unconnected-(U6-NC-Pad17)") (class "Default")
      (node (ref "U6") (pin "17") (pinfunction "NC_17") (pintype "passive+no_connect"))
    )
    (net (code "88") (name "unconnected-(U6-NC-Pad18)") (class "Default")
      (node (ref "U6") (pin "18") (pinfunction "NC_18") (pintype "passive+no_connect"))
    )
    (net (code "89") (name "unconnected-(U6-NC-Pad19)") (class "Default")
      (node (ref "U6") (pin "19") (pinfunction "NC_19") (pintype "passive+no_connect"))
    )
    (net (code "90") (name "unconnected-(U6-NC-Pad20)") (class "Default")
      (node (ref "U6") (pin "20") (pinfunction "NC_20") (pintype "passive+no_connect"))
    )
    (net (code "91") (name "unconnected-(U6-NC-Pad21)") (class "Default")
      (node (ref "U6") (pin "21") (pinfunction "NC_21") (pintype "passive+no_connect"))
    )
    (net (code "92") (name "unconnected-(U6-NC-Pad22)") (class "Default")
      (node (ref "U6") (pin "22") (pinfunction "NC_22") (pintype "passive+no_connect"))
    )
    (net (code "93") (name "unconnected-(U6-NC-Pad32)") (class "Default")
      (node (ref "U6") (pin "32") (pinfunction "NC_32") (pintype "passive+no_connect"))
    )
    (net (code "94") (name "unconnected-(U6-SENSOR_VN-Pad5)") (class "Default")
      (node (ref "U6") (pin "5") (pinfunction "SENSOR_VN_5") (pintype "passive"))
    )
    (net (code "95") (name "unconnected-(U6-SENSOR_VP-Pad4)") (class "Default")
      (node (ref "U6") (pin "4") (pinfunction "SENSOR_VP_4") (pintype "passive"))
    )
  )
)
